# Sound.net
KiCad netlist of a schematic drawn in Altium Designer
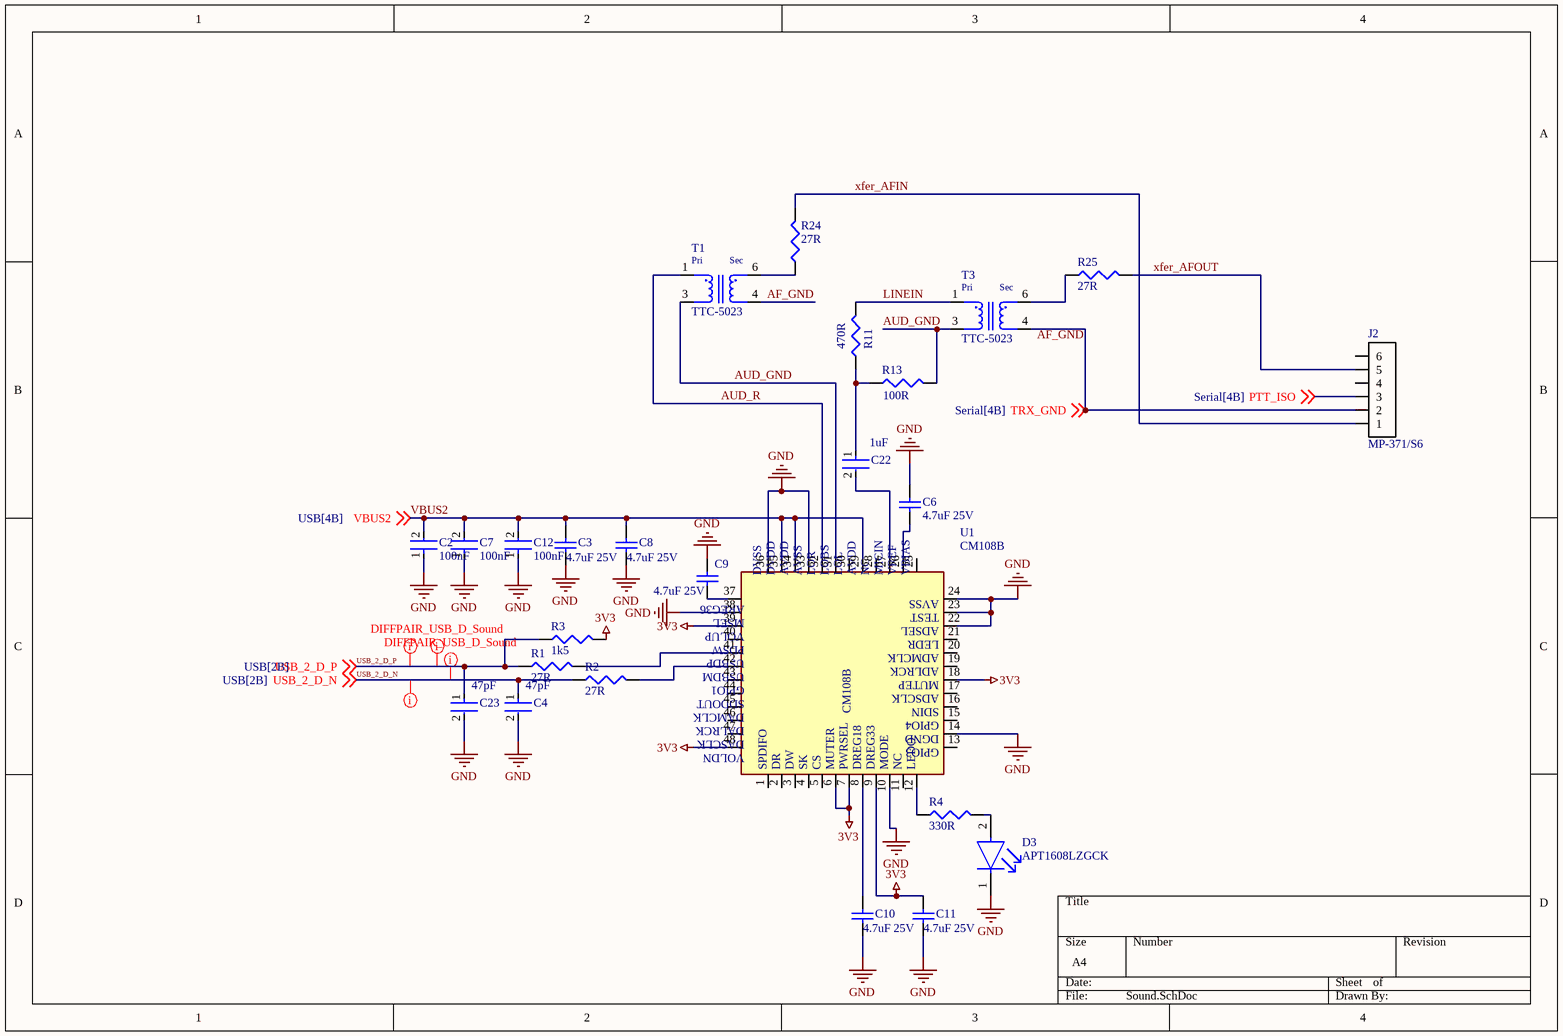
[diagram p0: Sound.SchDoc]

(export (version "E")
  (design (tool "Eeschema 10.0.6"))
  (components
    (comp (ref "C2")
      (value "CL10B104KC8NNNC")
      (footprint "FP-CL10-IPC_B")
      (description "Cap Ceramic 100nF 100V X7R ±10% Pad SMD 0603 +125°C T/R")
      (fields
        (field (name "TOLERANCE") "10%")
        (field (name "CAPACITANCE") "100nF")
        (field (name "JLCPCBPARTNUM") "C15725")
      )
      (libsource (lib "Altium Content Vault") (part "b4654b650e69147ec39a6b967a45e02"))
    )
    (comp (ref "C3")
      (value "4.7uF 25V")
      (footprint "CAPC1210(3225)220_M")
      (description "CAP 4.7uF 25V ±10% 1210 (3225 Metric) Thickness 2.2mm SMD")
      (fields (field (name "TOLERANCE") "Â±10%") (field (name "JLCPCBPARTNUM") "C86052"))
      (libsource (lib "Altium Content Vault") (part "CAP"))
    )
    (comp (ref "C4")
      (value "CL10C470JC8NNNC")
      (footprint "FP-CL10-IPC_C")
      (description "Cap Ceramic 47pF 100V C0G ±5% Pad SMD 0603 +125°C T/R")
      (fields
        (field (name "TOLERANCE") "5%")
        (field (name "CAPACITANCE") "47pF")
        (field (name "JLCPCBPARTNUM") "C1671")
      )
      (libsource (lib "Altium Content Vault") (part "b4654b650e69147ec39a6b967a45e02"))
    )
    (comp (ref "C6")
      (value "4.7uF 25V")
      (footprint "CAPC1210(3225)220_M")
      (description "CAP 4.7uF 25V ±10% 1210 (3225 Metric) Thickness 2.2mm SMD")
      (fields (field (name "TOLERANCE") "Â±10%") (field (name "JLCPCBPARTNUM") "C86052"))
      (libsource (lib "Altium Content Vault") (part "CAP"))
    )
    (comp (ref "C7")
      (value "CL10B104KC8NNNC")
      (footprint "FP-CL10-IPC_B")
      (description "Cap Ceramic 100nF 100V X7R ±10% Pad SMD 0603 +125°C T/R")
      (fields
        (field (name "TOLERANCE") "10%")
        (field (name "CAPACITANCE") "100nF")
        (field (name "JLCPCBPARTNUM") "C15725")
      )
      (libsource (lib "Altium Content Vault") (part "b4654b650e69147ec39a6b967a45e02"))
    )
    (comp (ref "C8")
      (value "4.7uF 25V")
      (footprint "CAPC1210(3225)220_M")
      (description "CAP 4.7uF 25V ±10% 1210 (3225 Metric) Thickness 2.2mm SMD")
      (fields (field (name "TOLERANCE") "Â±10%") (field (name "JLCPCBPARTNUM") "C86052"))
      (libsource (lib "Altium Content Vault") (part "CAP"))
    )
    (comp (ref "C9")
      (value "4.7uF 25V")
      (footprint "CAPC1210(3225)220_M")
      (description "CAP 4.7uF 25V ±10% 1210 (3225 Metric) Thickness 2.2mm SMD")
      (fields (field (name "TOLERANCE") "Â±10%") (field (name "JLCPCBPARTNUM") "C86052"))
      (libsource (lib "Altium Content Vault") (part "CAP"))
    )
    (comp (ref "C10")
      (value "4.7uF 25V")
      (footprint "CAPC1210(3225)220_M")
      (description "CAP 4.7uF 25V ±10% 1210 (3225 Metric) Thickness 2.2mm SMD")
      (fields (field (name "TOLERANCE") "Â±10%") (field (name "JLCPCBPARTNUM") "C86052"))
      (libsource (lib "Altium Content Vault") (part "CAP"))
    )
    (comp (ref "C11")
      (value "4.7uF 25V")
      (footprint "CAPC1210(3225)220_M")
      (description "CAP 4.7uF 25V ±10% 1210 (3225 Metric) Thickness 2.2mm SMD")
      (fields (field (name "TOLERANCE") "Â±10%") (field (name "JLCPCBPARTNUM") "C86052"))
      (libsource (lib "Altium Content Vault") (part "CAP"))
    )
    (comp (ref "C12")
      (value "CL10B104KC8NNNC")
      (footprint "FP-CL10-IPC_B")
      (description "Cap Ceramic 100nF 100V X7R ±10% Pad SMD 0603 +125°C T/R")
      (fields
        (field (name "TOLERANCE") "10%")
        (field (name "CAPACITANCE") "100nF")
        (field (name "JLCPCBPARTNUM") "C15725")
      )
      (libsource (lib "Altium Content Vault") (part "b4654b650e69147ec39a6b967a45e02"))
    )
    (comp (ref "C22")
      (value "CC0603KRX7R9BB105")
      (footprint "FP-CC0603-DB-MFG")
      (description "CAP CER 1UF 50V X7R 0603")
      (fields
        (field (name "TOLERANCE") "10%")
        (field (name "CAPACITANCE") "1uF")
        (field (name "JLCPCBPARTNUM") "C559769")
      )
      (libsource (lib "Altium Content Vault") (part "11868f565c42a9108669ba33697ecf6"))
    )
    (comp (ref "C23")
      (value "CL10C470JC8NNNC")
      (footprint "FP-CL10-IPC_C")
      (description "Cap Ceramic 47pF 100V C0G ±5% Pad SMD 0603 +125°C T/R")
      (fields
        (field (name "TOLERANCE") "5%")
        (field (name "CAPACITANCE") "47pF")
        (field (name "JLCPCBPARTNUM") "C1671")
      )
      (libsource (lib "Altium Content Vault") (part "b4654b650e69147ec39a6b967a45e02"))
    )
    (comp (ref "D3")
      (value "APT1608LZGCK")
      (footprint "FP-APT1608LZGCK-MFG")
      (description "LED GREEN CLEAR 2SMD")
      (fields (field (name "JLCPCBPARTNUM") "C1322302"))
      (libsource (lib "Altium Content Vault") (part "8706943c75ba83719d021d2fdc84c58"))
    )
    (comp (ref "J2")
      (value "MP-371/S6")
      (footprint "MiniDIN6_TopSolder_Lumberg")
      (description "Miniature circular connectors MP-371/S6")
      (fields (field (name "DIGIKEY_PARTNUM") "2057-MDP-006-ND"))
      (libsource (lib "MiniDin") (part "MiniDin6_SMT"))
    )
    (comp (ref "R1")
      (value "27R")
      (footprint "J1-0603")
      (description "Resistor")
      (fields (field (name "JLCPCBPARTNUM") "C192531") (field (name "PUBLISHER") "Altium Limited"))
      (libsource (lib "Miscellaneous Devices") (part "Res3"))
    )
    (comp (ref "R2")
      (value "27R")
      (footprint "J1-0603")
      (description "Resistor")
      (fields (field (name "JLCPCBPARTNUM") "C192531") (field (name "PUBLISHER") "Altium Limited"))
      (libsource (lib "Miscellaneous Devices") (part "Res3"))
    )
    (comp (ref "R3")
      (value "1k5")
      (footprint "J1-0603")
      (description "Resistor")
      (fields (field (name "JLCPCBPARTNUM") "C192164") (field (name "PUBLISHER") "Altium Limited"))
      (libsource (lib "Miscellaneous Devices") (part "Res3"))
    )
    (comp (ref "R4")
      (value "330R")
      (footprint "J1-0603")
      (description "Resistor")
      (fields (field (name "JLCPCBPARTNUM") "C23138") (field (name "PUBLISHER") "Altium Limited"))
      (libsource (lib "Miscellaneous Devices") (part "Res3"))
    )
    (comp (ref "R11")
      (value "470R")
      (footprint "J1-0603")
      (description "Resistor")
      (fields (field (name "JLCPCBPARTNUM") "C25804") (field (name "PUBLISHER") "Altium Limited"))
      (libsource (lib "Miscellaneous Devices") (part "Res3"))
    )
    (comp (ref "R13")
      (value "100R")
      (footprint "J1-0603")
      (description "Resistor")
      (fields (field (name "JLCPCBPARTNUM") "C22775") (field (name "PUBLISHER") "Altium Limited"))
      (libsource (lib "Miscellaneous Devices") (part "Res3"))
    )
    (comp (ref "R24")
      (value "27R")
      (footprint "J1-0603")
      (description "Resistor")
      (fields (field (name "JLCPCBPARTNUM") "C192531") (field (name "PUBLISHER") "Altium Limited"))
      (libsource (lib "Miscellaneous Devices") (part "Res3"))
    )
    (comp (ref "R25")
      (value "27R")
      (footprint "J1-0603")
      (description "Resistor")
      (fields (field (name "JLCPCBPARTNUM") "C192531") (field (name "PUBLISHER") "Altium Limited"))
      (libsource (lib "Miscellaneous Devices") (part "Res3"))
    )
    (comp (ref "T1")
      (value "TTC-5023")
      (footprint "TRANSFORMER_TTC-5023")
      (fields (field (name "MF") "Tamura") (field (name "JLCPCBPARTNUM") "C840532"))
      (libsource (lib "Torqeedo Workspace") (part "TTC-5023"))
    )
    (comp (ref "T3")
      (value "TTC-5023")
      (footprint "TRANSFORMER_TTC-5023")
      (fields (field (name "MF") "Tamura") (field (name "JLCPCBPARTNUM") "C840532"))
      (libsource (lib "Torqeedo Workspace") (part "TTC-5023"))
    )
    (comp (ref "U1")
      (value "CM108B")
      (footprint "TQFP48")
      (description "USB Audio Codec improved on CM")
      (fields (field (name "MF") "Cmedia") (field (name "JLCPCBPARTNUM") "C371347"))
      (libsource (lib "YaSIf") (part "CMP-002-000000-1"))
    )
  )
  (nets
    (net (code "1") (name "/AUD_GND") (class "Default")
      (node (ref "R13") (pin "2") (pinfunction "2_2") (pintype "passive"))
      (node (ref "T1") (pin "3") (pinfunction "3_3") (pintype "passive"))
      (node (ref "T3") (pin "3") (pinfunction "3_3") (pintype "passive"))
      (node (ref "U1") (pin "31") (pinfunction "31_31") (pintype "bidirectional"))
    )
    (net (code "2") (name "/AUD_R") (class "Default")
      (node (ref "T1") (pin "1") (pinfunction "1_1") (pintype "passive"))
      (node (ref "U1") (pin "32") (pinfunction "32_32") (pintype "bidirectional"))
    )
    (net (code "3") (name "/LINEIN") (class "Default")
      (node (ref "R11") (pin "2") (pinfunction "2_2") (pintype "passive"))
      (node (ref "T3") (pin "1") (pinfunction "1_1") (pintype "passive"))
    )
    (net (code "4") (name "/xfer_AFIN") (class "Default")
      (node (ref "J2") (pin "1") (pinfunction "1_1") (pintype "passive"))
      (node (ref "R24") (pin "2") (pinfunction "2_2") (pintype "passive"))
    )
    (net (code "5") (name "/xfer_AFOUT") (class "Default")
      (node (ref "J2") (pin "5") (pinfunction "5_5") (pintype "passive"))
      (node (ref "R25") (pin "2") (pinfunction "2_2") (pintype "passive"))
    )
    (net (code "6") (name "3V3") (class "Default")
      (node (ref "C11") (pin "2") (pinfunction "2_2") (pintype "passive"))
      (node (ref "R3") (pin "2") (pinfunction "2_2") (pintype "passive"))
      (node (ref "U1") (pin "18") (pinfunction "18_18") (pintype "bidirectional"))
      (node (ref "U1") (pin "39") (pinfunction "39_39") (pintype "bidirectional"))
      (node (ref "U1") (pin "48") (pinfunction "48_48") (pintype "bidirectional"))
      (node (ref "U1") (pin "6") (pinfunction "6_6") (pintype "bidirectional"))
      (node (ref "U1") (pin "7") (pinfunction "7_7") (pintype "bidirectional"))
      (node (ref "U1") (pin "9") (pinfunction "9_9") (pintype "bidirectional"))
    )
    (net (code "7") (name "GND") (class "Default")
      (node (ref "C10") (pin "1") (pinfunction "1_1") (pintype "passive"))
      (node (ref "C11") (pin "1") (pinfunction "1_1") (pintype "passive"))
      (node (ref "C12") (pin "1") (pinfunction "1_1") (pintype "passive"))
      (node (ref "C2") (pin "1") (pinfunction "1_1") (pintype "passive"))
      (node (ref "C23") (pin "2") (pinfunction "2_2") (pintype "passive"))
      (node (ref "C3") (pin "1") (pinfunction "1_1") (pintype "passive"))
      (node (ref "C4") (pin "2") (pinfunction "2_2") (pintype "passive"))
      (node (ref "C6") (pin "1") (pinfunction "1_1") (pintype "passive"))
      (node (ref "C7") (pin "1") (pinfunction "1_1") (pintype "passive"))
      (node (ref "C8") (pin "1") (pinfunction "1_1") (pintype "passive"))
      (node (ref "C9") (pin "2") (pinfunction "2_2") (pintype "passive"))
      (node (ref "D3") (pin "1") (pinfunction "C_1") (pintype "passive"))
      (node (ref "U1") (pin "10") (pinfunction "10_10") (pintype "bidirectional"))
      (node (ref "U1") (pin "14") (pinfunction "14_14") (pintype "bidirectional"))
      (node (ref "U1") (pin "22") (pinfunction "22_22") (pintype "bidirectional"))
      (node (ref "U1") (pin "23") (pinfunction "23_23") (pintype "bidirectional"))
      (node (ref "U1") (pin "24") (pinfunction "24_24") (pintype "bidirectional"))
      (node (ref "U1") (pin "33") (pinfunction "33_33") (pintype "bidirectional"))
      (node (ref "U1") (pin "36") (pinfunction "36_36") (pintype "bidirectional"))
      (node (ref "U1") (pin "38") (pinfunction "38_38") (pintype "bidirectional"))
    )
    (net (code "8") (name "Net-(C6-Pad2)") (class "Default")
      (node (ref "C6") (pin "2") (pinfunction "2_2") (pintype "passive"))
      (node (ref "U1") (pin "26") (pinfunction "26_26") (pintype "bidirectional"))
    )
    (net (code "9") (name "Net-(C9-Pad1)") (class "Default")
      (node (ref "C9") (pin "1") (pinfunction "1_1") (pintype "passive"))
      (node (ref "U1") (pin "37") (pinfunction "37_37") (pintype "bidirectional"))
    )
    (net (code "10") (name "Net-(C10-Pad2)") (class "Default")
      (node (ref "C10") (pin "2") (pinfunction "2_2") (pintype "passive"))
      (node (ref "U1") (pin "8") (pinfunction "8_8") (pintype "bidirectional"))
    )
    (net (code "11") (name "Net-(C22-Pad1)") (class "Default")
      (node (ref "C22") (pin "1") (pinfunction "1_1") (pintype "passive"))
      (node (ref "R11") (pin "1") (pinfunction "1_1") (pintype "passive"))
      (node (ref "R13") (pin "1") (pinfunction "1_1") (pintype "passive"))
    )
    (net (code "12") (name "Net-(C22-Pad2)") (class "Default")
      (node (ref "C22") (pin "2") (pinfunction "2_2") (pintype "passive"))
      (node (ref "U1") (pin "27") (pinfunction "27_27") (pintype "bidirectional"))
    )
    (net (code "13") (name "Net-(D3-A)") (class "Default")
      (node (ref "D3") (pin "2") (pinfunction "A_2") (pintype "passive"))
      (node (ref "R4") (pin "2") (pinfunction "2_2") (pintype "passive"))
    )
    (net (code "14") (name "Net-(R1-Pad2)") (class "Default")
      (node (ref "R1") (pin "2") (pinfunction "2_2") (pintype "passive"))
      (node (ref "U1") (pin "41") (pinfunction "41_41") (pintype "bidirectional"))
    )
    (net (code "15") (name "Net-(R2-Pad2)") (class "Default")
      (node (ref "R2") (pin "2") (pinfunction "2_2") (pintype "passive"))
      (node (ref "U1") (pin "42") (pinfunction "42_42") (pintype "bidirectional"))
    )
    (net (code "16") (name "Net-(R4-Pad1)") (class "Default")
      (node (ref "R4") (pin "1") (pinfunction "1_1") (pintype "passive"))
      (node (ref "U1") (pin "12") (pinfunction "12_12") (pintype "bidirectional"))
    )
    (net (code "17") (name "Net-(R24-Pad1)") (class "Default")
      (node (ref "R24") (pin "1") (pinfunction "1_1") (pintype "passive"))
      (node (ref "T1") (pin "6") (pinfunction "6_6") (pintype "passive"))
    )
    (net (code "18") (name "Net-(R25-Pad1)") (class "Default")
      (node (ref "R25") (pin "1") (pinfunction "1_1") (pintype "passive"))
      (node (ref "T3") (pin "6") (pinfunction "6_6") (pintype "passive"))
    )
    (net (code "19") (name "PTT_ISO") (class "Default")
      (node (ref "J2") (pin "3") (pinfunction "3_3") (pintype "passive"))
    )
    (net (code "20") (name "TRX_GND") (class "Default")
      (node (ref "J2") (pin "2") (pinfunction "2_2") (pintype "passive"))
      (node (ref "T1") (pin "4") (pinfunction "4_4") (pintype "passive"))
      (node (ref "T3") (pin "4") (pinfunction "4_4") (pintype "passive"))
    )
    (net (code "21") (name "USB_2_D_N") (class "Default")
      (node (ref "C4") (pin "1") (pinfunction "1_1") (pintype "passive"))
      (node (ref "R2") (pin "1") (pinfunction "1_1") (pintype "passive"))
    )
    (net (code "22") (name "USB_2_D_P") (class "Default")
      (node (ref "C23") (pin "1") (pinfunction "1_1") (pintype "passive"))
      (node (ref "R1") (pin "1") (pinfunction "1_1") (pintype "passive"))
      (node (ref "R3") (pin "1") (pinfunction "1_1") (pintype "passive"))
    )
    (net (code "23") (name "VBUS2") (class "Default")
      (node (ref "C12") (pin "2") (pinfunction "2_2") (pintype "passive"))
      (node (ref "C2") (pin "2") (pinfunction "2_2") (pintype "passive"))
      (node (ref "C3") (pin "2") (pinfunction "2_2") (pintype "passive"))
      (node (ref "C7") (pin "2") (pinfunction "2_2") (pintype "passive"))
      (node (ref "C8") (pin "2") (pinfunction "2_2") (pintype "passive"))
      (node (ref "U1") (pin "29") (pinfunction "29_29") (pintype "bidirectional"))
      (node (ref "U1") (pin "34") (pinfunction "34_34") (pintype "bidirectional"))
      (node (ref "U1") (pin "35") (pinfunction "35_35") (pintype "bidirectional"))
    )
    (net (code "24") (name "unconnected-(J2-Pad4)") (class "Default")
      (node (ref "J2") (pin "4") (pinfunction "4_4") (pintype "passive"))
    )
    (net (code "25") (name "unconnected-(J2-Pad6)") (class "Default")
      (node (ref "J2") (pin "6") (pinfunction "6_6") (pintype "passive"))
    )
    (net (code "26") (name "unconnected-(U1-Pad1)") (class "Default")
      (node (ref "U1") (pin "1") (pinfunction "1_1") (pintype "bidirectional"))
    )
    (net (code "27") (name "unconnected-(U1-Pad2)") (class "Default")
      (node (ref "U1") (pin "2") (pinfunction "2_2") (pintype "bidirectional"))
    )
    (net (code "28") (name "unconnected-(U1-Pad3)") (class "Default")
      (node (ref "U1") (pin "3") (pinfunction "3_3") (pintype "bidirectional"))
    )
    (net (code "29") (name "unconnected-(U1-Pad4)") (class "Default")
      (node (ref "U1") (pin "4") (pinfunction "4_4") (pintype "bidirectional"))
    )
    (net (code "30") (name "unconnected-(U1-Pad5)") (class "Default")
      (node (ref "U1") (pin "5") (pinfunction "5_5") (pintype "bidirectional"))
    )
    (net (code "31") (name "unconnected-(U1-Pad11)") (class "Default")
      (node (ref "U1") (pin "11") (pinfunction "11_11") (pintype "bidirectional"))
    )
    (net (code "32") (name "unconnected-(U1-Pad13)") (class "Default")
      (node (ref "U1") (pin "13") (pinfunction "13_13") (pintype "bidirectional"))
    )
    (net (code "33") (name "unconnected-(U1-Pad15)") (class "Default")
      (node (ref "U1") (pin "15") (pinfunction "15_15") (pintype "bidirectional"))
    )
    (net (code "34") (name "unconnected-(U1-Pad16)") (class "Default")
      (node (ref "U1") (pin "16") (pinfunction "16_16") (pintype "bidirectional"))
    )
    (net (code "35") (name "unconnected-(U1-Pad17)") (class "Default")
      (node (ref "U1") (pin "17") (pinfunction "17_17") (pintype "bidirectional"))
    )
    (net (code "36") (name "unconnected-(U1-Pad19)") (class "Default")
      (node (ref "U1") (pin "19") (pinfunction "19_19") (pintype "bidirectional"))
    )
    (net (code "37") (name "unconnected-(U1-Pad20)") (class "Default")
      (node (ref "U1") (pin "20") (pinfunction "20_20") (pintype "bidirectional"))
    )
    (net (code "38") (name "unconnected-(U1-Pad21)") (class "Default")
      (node (ref "U1") (pin "21") (pinfunction "21_21") (pintype "bidirectional"))
    )
    (net (code "39") (name "unconnected-(U1-Pad25)") (class "Default")
      (node (ref "U1") (pin "25") (pinfunction "25_25") (pintype "bidirectional"))
    )
    (net (code "40") (name "unconnected-(U1-Pad28)") (class "Default")
      (node (ref "U1") (pin "28") (pinfunction "28_28") (pintype "bidirectional"))
    )
    (net (code "41") (name "unconnected-(U1-Pad30)") (class "Default")
      (node (ref "U1") (pin "30") (pinfunction "30_30") (pintype "bidirectional"))
    )
    (net (code "42") (name "unconnected-(U1-Pad40)") (class "Default")
      (node (ref "U1") (pin "40") (pinfunction "40_40") (pintype "bidirectional"))
    )
    (net (code "43") (name "unconnected-(U1-Pad43)") (class "Default")
      (node (ref "U1") (pin "43") (pinfunction "43_43") (pintype "bidirectional"))
    )
    (net (code "44") (name "unconnected-(U1-Pad44)") (class "Default")
      (node (ref "U1") (pin "44") (pinfunction "44_44") (pintype "bidirectional"))
    )
    (net (code "45") (name "unconnected-(U1-Pad45)") (class "Default")
      (node (ref "U1") (pin "45") (pinfunction "45_45") (pintype "bidirectional"))
    )
    (net (code "46") (name "unconnected-(U1-Pad46)") (class "Default")
      (node (ref "U1") (pin "46") (pinfunction "46_46") (pintype "bidirectional"))
    )
    (net (code "47") (name "unconnected-(U1-Pad47)") (class "Default")
      (node (ref "U1") (pin "47") (pinfunction "47_47") (pintype "bidirectional"))
    )
  )
)
